# PowerSupply.net
KiCad netlist of a schematic drawn in Altium Designer
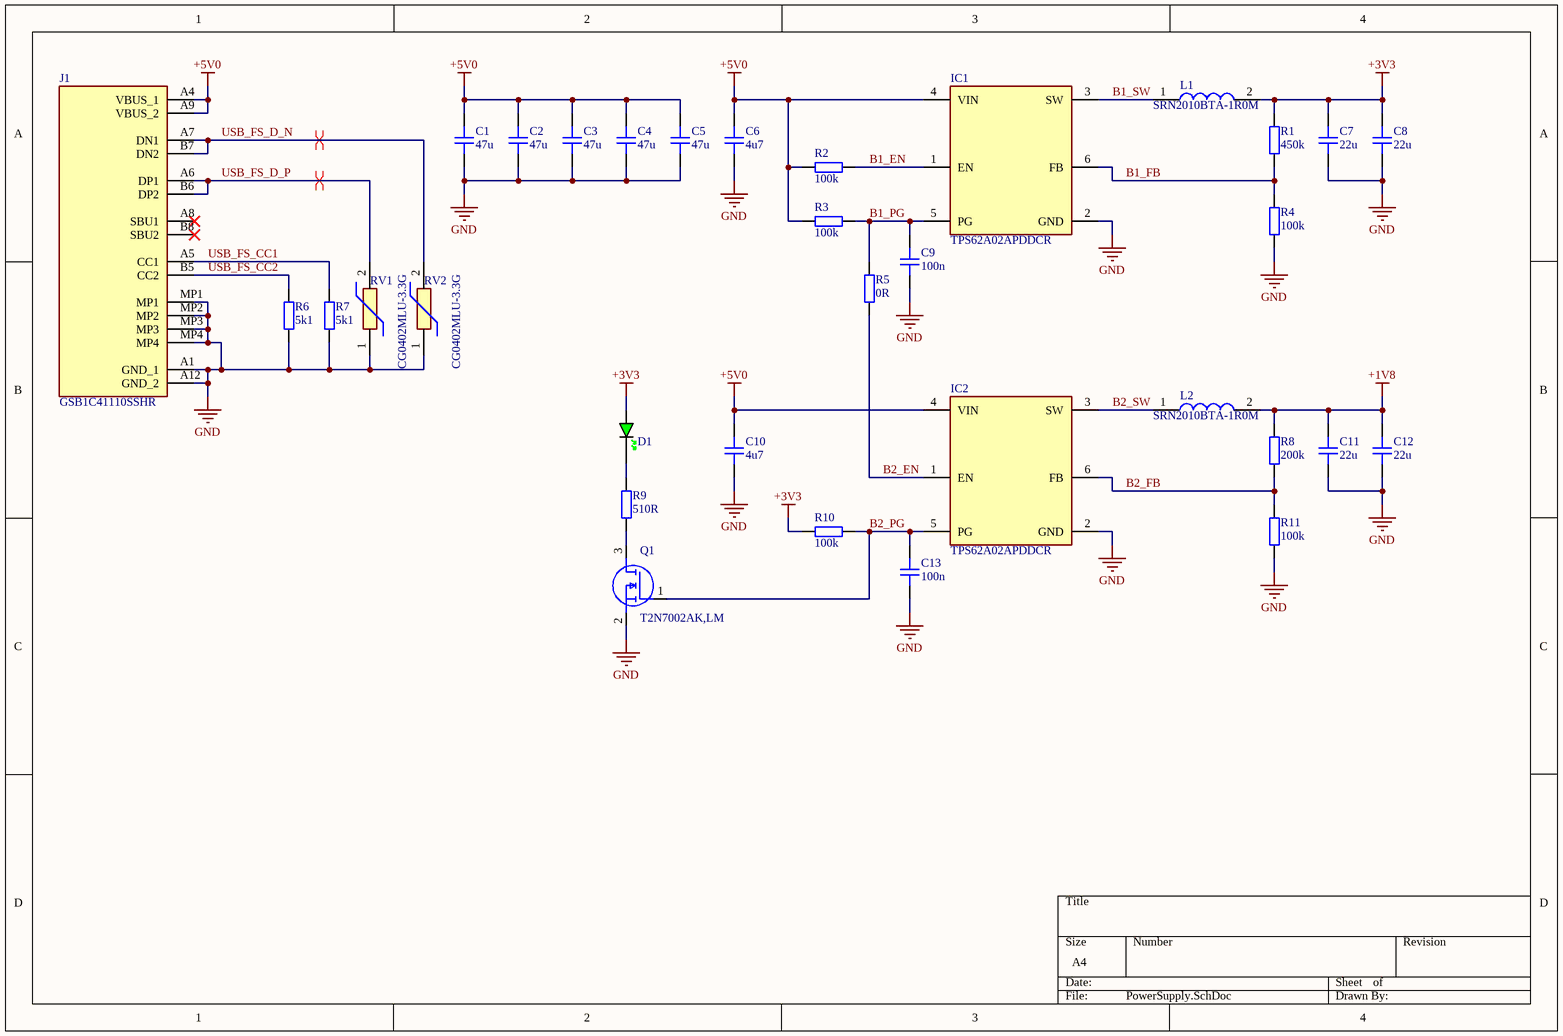
[diagram p0: PowerSupply.SchDoc]

(export (version "E")
  (design (tool "Eeschema 10.0.6"))
  (components
    (comp (ref "C1")
      (value "47u")
      (footprint "CAP_1210")
      (description "Capacitor SMD 1210")
      (libsource (lib "Schematic-Lib-PhilsLab") (part "CAP_1210"))
    )
    (comp (ref "C2")
      (value "47u")
      (footprint "CAP_1210")
      (description "Capacitor SMD 1210")
      (libsource (lib "Schematic-Lib-PhilsLab") (part "CAP_1210"))
    )
    (comp (ref "C3")
      (value "47u")
      (footprint "CAP_1210")
      (description "Capacitor SMD 1210")
      (libsource (lib "Schematic-Lib-PhilsLab") (part "CAP_1210"))
    )
    (comp (ref "C4")
      (value "47u")
      (footprint "CAP_1210")
      (description "Capacitor SMD 1210")
      (libsource (lib "Schematic-Lib-PhilsLab") (part "CAP_1210"))
    )
    (comp (ref "C5")
      (value "47u")
      (footprint "CAP_1210")
      (description "Capacitor SMD 1210")
      (libsource (lib "Schematic-Lib-PhilsLab") (part "CAP_1210"))
    )
    (comp (ref "C6")
      (value "4u7")
      (footprint "CAP_0603")
      (description "Capacitor SMD 0603")
      (libsource (lib "Schematic-Lib-PhilsLab") (part "CAP_0603"))
    )
    (comp (ref "C7")
      (value "22u")
      (footprint "CAP_0603")
      (description "Capacitor SMD 0603")
      (libsource (lib "Schematic-Lib-PhilsLab") (part "CAP_0603"))
    )
    (comp (ref "C8")
      (value "22u")
      (footprint "CAP_0603")
      (description "Capacitor SMD 0603")
      (libsource (lib "Schematic-Lib-PhilsLab") (part "CAP_0603"))
    )
    (comp (ref "C9")
      (value "100n")
      (footprint "CAP_0402")
      (description "Capacitor SMD 0402")
      (libsource (lib "Schematic-Lib-PhilsLab") (part "CAP_0402"))
    )
    (comp (ref "C10")
      (value "4u7")
      (footprint "CAP_0603")
      (description "Capacitor SMD 0603")
      (libsource (lib "Schematic-Lib-PhilsLab") (part "CAP_0603"))
    )
    (comp (ref "C11")
      (value "22u")
      (footprint "CAP_0603")
      (description "Capacitor SMD 0603")
      (libsource (lib "Schematic-Lib-PhilsLab") (part "CAP_0603"))
    )
    (comp (ref "C12")
      (value "22u")
      (footprint "CAP_0603")
      (description "Capacitor SMD 0603")
      (libsource (lib "Schematic-Lib-PhilsLab") (part "CAP_0603"))
    )
    (comp (ref "C13")
      (value "100n")
      (footprint "CAP_0402")
      (description "Capacitor SMD 0402")
      (libsource (lib "Schematic-Lib-PhilsLab") (part "CAP_0402"))
    )
    (comp (ref "D1")
      (value "GREEN")
      (footprint "LED_0603_GREEN")
      (description "LED 0603 GREEN SMD")
      (libsource (lib "Schematic-Lib-PhilsLab") (part "LED_0603_GREEN"))
    )
    (comp (ref "IC1")
      (value "TPS62A02APDDCR")
      (footprint "Footprint-Lib-PhilsLab:SOT95P280X110-6N - duplicate")
      (description "Integrated Circuit")
      (fields (field (name "MOUSER PART NUMBER") "595-TPS62A02APDDCR"))
      (libsource (lib "Schematic-Lib-PhilsLab") (part "TPS62A02APDDCR"))
    )
    (comp (ref "IC2")
      (value "TPS62A02APDDCR")
      (footprint "Footprint-Lib-PhilsLab:SOT95P280X110-6N - duplicate")
      (description "Integrated Circuit")
      (fields (field (name "MOUSER PART NUMBER") "595-TPS62A02APDDCR"))
      (libsource (lib "Schematic-Lib-PhilsLab") (part "TPS62A02APDDCR"))
    )
    (comp (ref "J1")
      (value "GSB1C41110SSHR")
      (footprint "Footprint-Lib-PhilsLab:GSB1C41110SSHR")
      (description "Connector")
      (libsource (lib "Schematic-Lib-PhilsLab") (part "GSB1C41110SSHR"))
    )
    (comp (ref "L1")
      (value "SRN2010BTA-1R0M")
      (footprint "Footprint-Lib-PhilsLab:SRN2010BTA1R0M")
      (description "Inductor")
      (libsource (lib "Schematic-Lib-PhilsLab") (part "SRN2010BTA-1R0M"))
    )
    (comp (ref "L2")
      (value "SRN2010BTA-1R0M")
      (footprint "Footprint-Lib-PhilsLab:SRN2010BTA1R0M")
      (description "Inductor")
      (libsource (lib "Schematic-Lib-PhilsLab") (part "SRN2010BTA-1R0M"))
    )
    (comp (ref "Q1")
      (value "T2N7002AK,LM")
      (footprint "Footprint-Lib-PhilsLab:TBAT54CLM")
      (description "MOSFET (N-Channel)")
      (fields (field (name "MOUSER PART NUMBER") "757-T2N7002AKLM"))
      (libsource (lib "Schematic-Lib-PhilsLab") (part "T2N7002AK,LM"))
    )
    (comp (ref "R1")
      (value "450k")
      (footprint "RES_0402")
      (description "Resistor SMD 0402")
      (libsource (lib "Schematic-Lib-PhilsLab") (part "RES_0402"))
    )
    (comp (ref "R2")
      (value "100k")
      (footprint "RES_0402")
      (description "Resistor SMD 0402")
      (libsource (lib "Schematic-Lib-PhilsLab") (part "RES_0402"))
    )
    (comp (ref "R3")
      (value "100k")
      (footprint "RES_0402")
      (description "Resistor SMD 0402")
      (libsource (lib "Schematic-Lib-PhilsLab") (part "RES_0402"))
    )
    (comp (ref "R4")
      (value "100k")
      (footprint "RES_0402")
      (description "Resistor SMD 0402")
      (libsource (lib "Schematic-Lib-PhilsLab") (part "RES_0402"))
    )
    (comp (ref "R5")
      (value "0R")
      (footprint "RES_0402")
      (description "Resistor SMD 0402")
      (libsource (lib "Schematic-Lib-PhilsLab") (part "RES_0402"))
    )
    (comp (ref "R6")
      (value "5k1")
      (footprint "RES_0402")
      (description "Resistor SMD 0402")
      (libsource (lib "Schematic-Lib-PhilsLab") (part "RES_0402"))
    )
    (comp (ref "R7")
      (value "5k1")
      (footprint "RES_0402")
      (description "Resistor SMD 0402")
      (libsource (lib "Schematic-Lib-PhilsLab") (part "RES_0402"))
    )
    (comp (ref "R8")
      (value "200k")
      (footprint "RES_0402")
      (description "Resistor SMD 0402")
      (libsource (lib "Schematic-Lib-PhilsLab") (part "RES_0402"))
    )
    (comp (ref "R9")
      (value "510R")
      (footprint "RES_0603")
      (description "Resistor SMD 0603")
      (libsource (lib "Schematic-Lib-PhilsLab") (part "RES_0603"))
    )
    (comp (ref "R10")
      (value "100k")
      (footprint "RES_0402")
      (description "Resistor SMD 0402")
      (libsource (lib "Schematic-Lib-PhilsLab") (part "RES_0402"))
    )
    (comp (ref "R11")
      (value "100k")
      (footprint "RES_0402")
      (description "Resistor SMD 0402")
      (libsource (lib "Schematic-Lib-PhilsLab") (part "RES_0402"))
    )
    (comp (ref "RV1")
      (value "CG0402MLU-3.3G")
      (footprint "Footprint-Lib-PhilsLab:VARC1005X41N")
      (description "ESD Diode")
      (fields (field (name "MOUSER PART NUMBER") "652-CG0402MLU-3.3G"))
      (libsource (lib "Schematic-Lib-PhilsLab") (part "CG0402MLU-3.3G"))
    )
    (comp (ref "RV2")
      (value "CG0402MLU-3.3G")
      (footprint "Footprint-Lib-PhilsLab:VARC1005X41N")
      (description "ESD Diode")
      (fields (field (name "MOUSER PART NUMBER") "652-CG0402MLU-3.3G"))
      (libsource (lib "Schematic-Lib-PhilsLab") (part "CG0402MLU-3.3G"))
    )
  )
  (nets
    (net (code "1") (name "+1V8") (class "Default")
      (node (ref "C11") (pin "2") (pinfunction "2_2") (pintype "passive"))
      (node (ref "C12") (pin "2") (pinfunction "2_2") (pintype "passive"))
      (node (ref "L2") (pin "2") (pinfunction "2_2") (pintype "passive"))
      (node (ref "R8") (pin "2") (pinfunction "2_2") (pintype "passive"))
    )
    (net (code "2") (name "+3V3") (class "Default")
      (node (ref "C7") (pin "2") (pinfunction "2_2") (pintype "passive"))
      (node (ref "C8") (pin "2") (pinfunction "2_2") (pintype "passive"))
      (node (ref "D1") (pin "A") (pinfunction "A_A") (pintype "passive"))
      (node (ref "L1") (pin "2") (pinfunction "2_2") (pintype "passive"))
      (node (ref "R1") (pin "2") (pinfunction "2_2") (pintype "passive"))
      (node (ref "R10") (pin "1") (pinfunction "1_1") (pintype "passive"))
    )
    (net (code "3") (name "+5V0") (class "Default")
      (node (ref "C1") (pin "2") (pinfunction "2_2") (pintype "passive"))
      (node (ref "C10") (pin "2") (pinfunction "2_2") (pintype "passive"))
      (node (ref "C2") (pin "2") (pinfunction "2_2") (pintype "passive"))
      (node (ref "C3") (pin "2") (pinfunction "2_2") (pintype "passive"))
      (node (ref "C4") (pin "2") (pinfunction "2_2") (pintype "passive"))
      (node (ref "C5") (pin "2") (pinfunction "2_2") (pintype "passive"))
      (node (ref "C6") (pin "2") (pinfunction "2_2") (pintype "passive"))
      (node (ref "IC1") (pin "4") (pinfunction "VIN_4") (pintype "passive"))
      (node (ref "IC2") (pin "4") (pinfunction "VIN_4") (pintype "passive"))
      (node (ref "J1") (pin "A4") (pinfunction "VBUS_1_A4") (pintype "passive"))
      (node (ref "J1") (pin "A9") (pinfunction "VBUS_2_A9") (pintype "passive"))
      (node (ref "R2") (pin "1") (pinfunction "1_1") (pintype "passive"))
      (node (ref "R3") (pin "1") (pinfunction "1_1") (pintype "passive"))
    )
    (net (code "4") (name "/B1_EN") (class "Default")
      (node (ref "IC1") (pin "1") (pinfunction "EN_1") (pintype "passive"))
      (node (ref "R2") (pin "2") (pinfunction "2_2") (pintype "passive"))
    )
    (net (code "5") (name "/B1_FB") (class "Default")
      (node (ref "IC1") (pin "6") (pinfunction "FB_6") (pintype "passive"))
      (node (ref "R1") (pin "1") (pinfunction "1_1") (pintype "passive"))
      (node (ref "R4") (pin "2") (pinfunction "2_2") (pintype "passive"))
    )
    (net (code "6") (name "/B1_PG") (class "Default")
      (node (ref "C9") (pin "2") (pinfunction "2_2") (pintype "passive"))
      (node (ref "IC1") (pin "5") (pinfunction "PG_5") (pintype "passive"))
      (node (ref "R3") (pin "2") (pinfunction "2_2") (pintype "passive"))
      (node (ref "R5") (pin "2") (pinfunction "2_2") (pintype "passive"))
    )
    (net (code "7") (name "/B1_SW") (class "Default")
      (node (ref "IC1") (pin "3") (pinfunction "SW_3") (pintype "passive"))
      (node (ref "L1") (pin "1") (pinfunction "1_1") (pintype "passive"))
    )
    (net (code "8") (name "/B2_EN") (class "Default")
      (node (ref "IC2") (pin "1") (pinfunction "EN_1") (pintype "passive"))
      (node (ref "R5") (pin "1") (pinfunction "1_1") (pintype "passive"))
    )
    (net (code "9") (name "/B2_FB") (class "Default")
      (node (ref "IC2") (pin "6") (pinfunction "FB_6") (pintype "passive"))
      (node (ref "R11") (pin "2") (pinfunction "2_2") (pintype "passive"))
      (node (ref "R8") (pin "1") (pinfunction "1_1") (pintype "passive"))
    )
    (net (code "10") (name "/B2_PG") (class "Default")
      (node (ref "C13") (pin "2") (pinfunction "2_2") (pintype "passive"))
      (node (ref "IC2") (pin "5") (pinfunction "PG_5") (pintype "passive"))
      (node (ref "Q1") (pin "1") (pinfunction "G_1") (pintype "passive"))
      (node (ref "R10") (pin "2") (pinfunction "2_2") (pintype "passive"))
    )
    (net (code "11") (name "/B2_SW") (class "Default")
      (node (ref "IC2") (pin "3") (pinfunction "SW_3") (pintype "passive"))
      (node (ref "L2") (pin "1") (pinfunction "1_1") (pintype "passive"))
    )
    (net (code "12") (name "/USB_FS_CC1") (class "Default")
      (node (ref "J1") (pin "A5") (pinfunction "CC1_A5") (pintype "passive"))
      (node (ref "R7") (pin "1") (pinfunction "1_1") (pintype "passive"))
    )
    (net (code "13") (name "/USB_FS_CC2") (class "Default")
      (node (ref "J1") (pin "B5") (pinfunction "CC2_B5") (pintype "passive"))
      (node (ref "R6") (pin "1") (pinfunction "1_1") (pintype "passive"))
    )
    (net (code "14") (name "/USB_FS_D_N") (class "Default")
      (node (ref "J1") (pin "A7") (pinfunction "DN1_A7") (pintype "passive"))
      (node (ref "J1") (pin "B7") (pinfunction "DN2_B7") (pintype "passive"))
      (node (ref "RV2") (pin "2") (pinfunction "2_2") (pintype "passive"))
    )
    (net (code "15") (name "/USB_FS_D_P") (class "Default")
      (node (ref "J1") (pin "A6") (pinfunction "DP1_A6") (pintype "passive"))
      (node (ref "J1") (pin "B6") (pinfunction "DP2_B6") (pintype "passive"))
      (node (ref "RV1") (pin "2") (pinfunction "2_2") (pintype "passive"))
    )
    (net (code "16") (name "GND") (class "Default")
      (node (ref "C1") (pin "1") (pinfunction "1_1") (pintype "passive"))
      (node (ref "C10") (pin "1") (pinfunction "1_1") (pintype "passive"))
      (node (ref "C11") (pin "1") (pinfunction "1_1") (pintype "passive"))
      (node (ref "C12") (pin "1") (pinfunction "1_1") (pintype "passive"))
      (node (ref "C13") (pin "1") (pinfunction "1_1") (pintype "passive"))
      (node (ref "C2") (pin "1") (pinfunction "1_1") (pintype "passive"))
      (node (ref "C3") (pin "1") (pinfunction "1_1") (pintype "passive"))
      (node (ref "C4") (pin "1") (pinfunction "1_1") (pintype "passive"))
      (node (ref "C5") (pin "1") (pinfunction "1_1") (pintype "passive"))
      (node (ref "C6") (pin "1") (pinfunction "1_1") (pintype "passive"))
      (node (ref "C7") (pin "1") (pinfunction "1_1") (pintype "passive"))
      (node (ref "C8") (pin "1") (pinfunction "1_1") (pintype "passive"))
      (node (ref "C9") (pin "1") (pinfunction "1_1") (pintype "passive"))
      (node (ref "IC1") (pin "2") (pinfunction "GND_2") (pintype "passive"))
      (node (ref "IC2") (pin "2") (pinfunction "GND_2") (pintype "passive"))
      (node (ref "J1") (pin "A1") (pinfunction "GND_1_A1") (pintype "passive"))
      (node (ref "J1") (pin "A12") (pinfunction "GND_2_A12") (pintype "passive"))
      (node (ref "J1") (pin "MP1") (pinfunction "MP1_MP1") (pintype "passive"))
      (node (ref "J1") (pin "MP2") (pinfunction "MP2_MP2") (pintype "passive"))
      (node (ref "J1") (pin "MP3") (pinfunction "MP3_MP3") (pintype "passive"))
      (node (ref "J1") (pin "MP4") (pinfunction "MP4_MP4") (pintype "passive"))
      (node (ref "Q1") (pin "2") (pinfunction "S_2") (pintype "passive"))
      (node (ref "R11") (pin "1") (pinfunction "1_1") (pintype "passive"))
      (node (ref "R4") (pin "1") (pinfunction "1_1") (pintype "passive"))
      (node (ref "R6") (pin "2") (pinfunction "2_2") (pintype "passive"))
      (node (ref "R7") (pin "2") (pinfunction "2_2") (pintype "passive"))
      (node (ref "RV1") (pin "1") (pinfunction "1_1") (pintype "passive"))
      (node (ref "RV2") (pin "1") (pinfunction "1_1") (pintype "passive"))
    )
    (net (code "17") (name "Net-(D1-PadK)") (class "Default")
      (node (ref "D1") (pin "K") (pinfunction "K_K") (pintype "passive"))
      (node (ref "R9") (pin "2") (pinfunction "2_2") (pintype "passive"))
    )
    (net (code "18") (name "Net-(Q1-D)") (class "Default")
      (node (ref "Q1") (pin "3") (pinfunction "D_3") (pintype "passive"))
      (node (ref "R9") (pin "1") (pinfunction "1_1") (pintype "passive"))
    )
    (net (code "19") (name "unconnected-(J1-SBU1-PadA8)") (class "Default")
      (node (ref "J1") (pin "A8") (pinfunction "SBU1_A8") (pintype "passive+no_connect"))
    )
    (net (code "20") (name "unconnected-(J1-SBU2-PadB8)") (class "Default")
      (node (ref "J1") (pin "B8") (pinfunction "SBU2_B8") (pintype "passive+no_connect"))
    )
  )
)
